# Shematic.net
KiCad netlist of a schematic drawn in Altium Designer
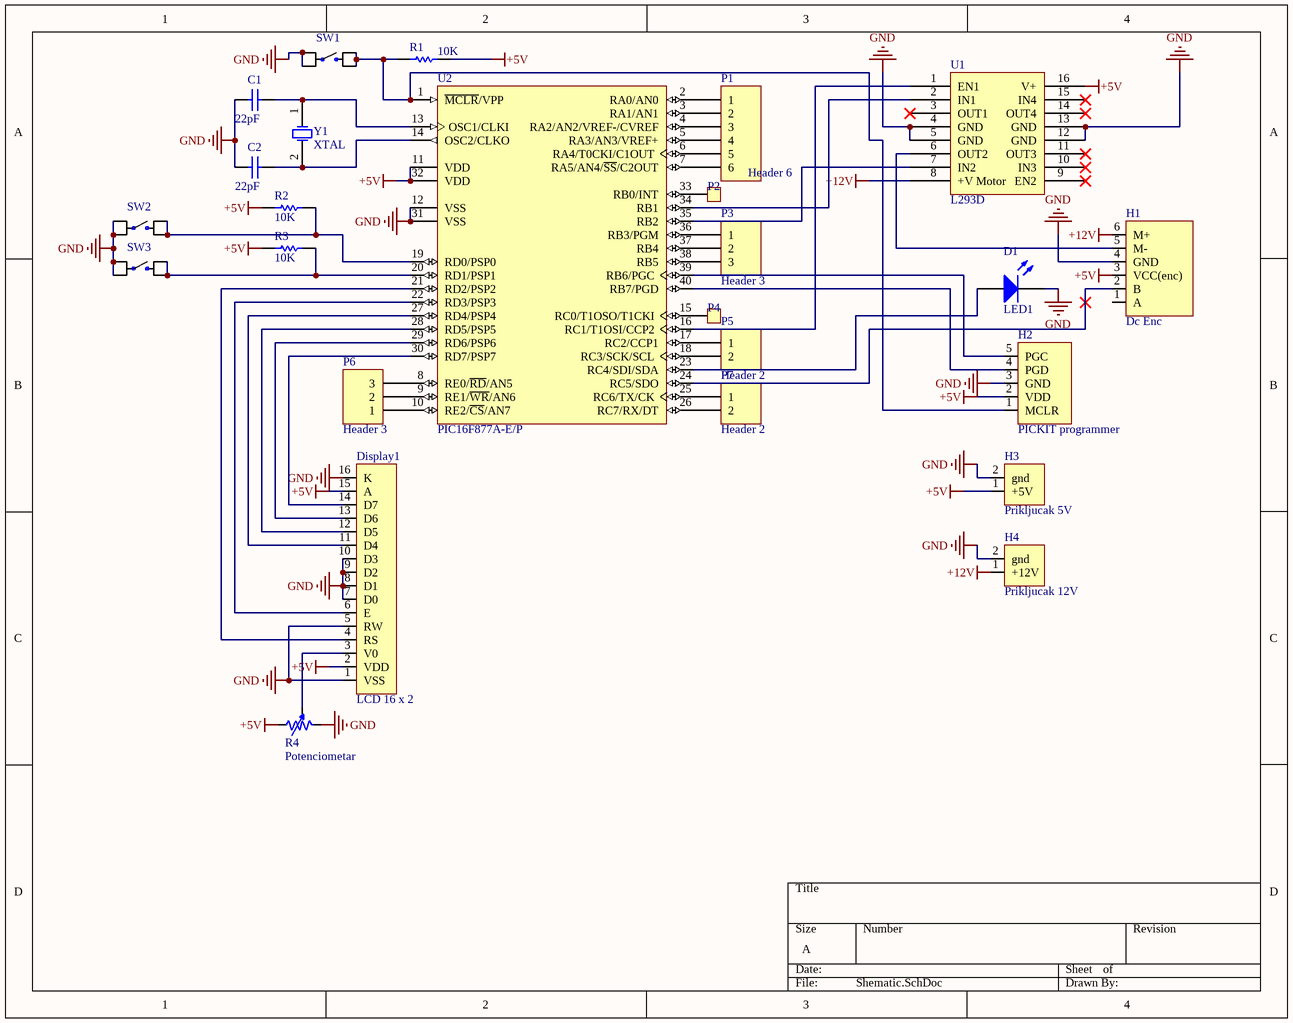
[diagram p0: Shematic.SchDoc]

(export (version "E")
  (design (tool "Eeschema 10.0.6"))
  (components
    (comp (ref "C1")
      (value "22pF")
      (footprint "RAD-0.3")
      (description "Capacitor")
      (fields (field (name "Comment") "Cap") (field (name "PUBLISHER") "Altium Limited"))
      (libsource (lib "Miscellaneous Devices") (part "Cap"))
    )
    (comp (ref "C2")
      (value "22pF")
      (footprint "RAD-0.3")
      (description "Capacitor")
      (fields (field (name "Comment") "Cap") (field (name "PUBLISHER") "Altium Limited"))
      (libsource (lib "Miscellaneous Devices") (part "Cap"))
    )
    (comp (ref "D1")
      (value "LED1")
      (footprint "LED-1")
      (description "Typical RED GaAs LED")
      (fields (field (name "PUBLISHER") "Altium Limited"))
      (libsource (lib "Miscellaneous Devices") (part "LED1"))
    )
    (comp (ref "Display1")
      (value "LCD 16 x 2")
      (footprint "LCD16x2")
      (libsource (lib "Shematic-LIB") (part "LCD 16 X 2"))
    )
    (comp (ref "H1") (value "Dc Enc") (libsource (lib "Shematic-LIB") (part "Header DC & ENC")))
    (comp (ref "H2")
      (value "PICKIT programmer")
      (footprint "Pickit")
      (libsource (lib "Shematic-LIB") (part "PICKIT HEADER"))
    )
    (comp (ref "H3")
      (value "Prikljucak 5V")
      (footprint "H 5V")
      (libsource (lib "Shematic-LIB") (part "Header 5V"))
    )
    (comp (ref "H4")
      (value "Prikljucak 12V")
      (footprint "H 12V")
      (libsource (lib "Shematic-LIB") (part "Header 12V"))
    )
    (comp (ref "P1")
      (value "Header 6")
      (footprint "HDR1X6")
      (description "Header, 6-Pin")
      (fields (field (name "PUBLISHER") "Altium Limited"))
      (libsource (lib "Miscellaneous Connectors") (part "Header 6"))
    )
    (comp (ref "P2")
      (value "Header 1")
      (footprint "Header 1")
      (libsource (lib "Shematic-LIB") (part "Header 1"))
    )
    (comp (ref "P3")
      (value "Header 3")
      (footprint "HDR1X3")
      (description "Header, 3-Pin")
      (fields (field (name "PUBLISHER") "Altium Limited"))
      (libsource (lib "") (part "Header 3_1"))
    )
    (comp (ref "P4")
      (value "Header 1")
      (footprint "Header 1")
      (libsource (lib "Shematic-LIB") (part "Header 1"))
    )
    (comp (ref "P5")
      (value "Header 2")
      (footprint "HDR1X2")
      (description "Header, 2-Pin")
      (fields (field (name "PUBLISHER") "Altium Limited"))
      (libsource (lib "Miscellaneous Connectors") (part "Header 2"))
    )
    (comp (ref "P6")
      (value "Header 3")
      (footprint "HDR1X3")
      (description "Header, 3-Pin")
      (fields (field (name "PUBLISHER") "Altium Limited"))
      (libsource (lib "Miscellaneous Connectors") (part "Header 3"))
    )
    (comp (ref "P7")
      (value "Header 2")
      (footprint "HDR1X2")
      (description "Header, 2-Pin")
      (fields (field (name "PUBLISHER") "Altium Limited"))
      (libsource (lib "Miscellaneous Connectors") (part "Header 2"))
    )
    (comp (ref "R1")
      (value "10K")
      (footprint "AXIAL-0.3")
      (description "Resistor")
      (fields (field (name "Comment") "Res1") (field (name "PUBLISHER") "Altium Limited"))
      (libsource (lib "Miscellaneous Devices") (part "Res1"))
    )
    (comp (ref "R2")
      (value "10K")
      (footprint "AXIAL-0.3")
      (description "Resistor")
      (fields (field (name "Comment") "Res1") (field (name "PUBLISHER") "Altium Limited"))
      (libsource (lib "Miscellaneous Devices") (part "Res1"))
    )
    (comp (ref "R3")
      (value "10K")
      (footprint "AXIAL-0.3")
      (description "Resistor")
      (fields (field (name "Comment") "Res1") (field (name "PUBLISHER") "Altium Limited"))
      (libsource (lib "Miscellaneous Devices") (part "Res1"))
    )
    (comp (ref "R4")
      (value "Potenciometar")
      (footprint "ADJ_RES")
      (libsource (lib "Shematic-LIB") (part "ADJ_RES"))
    )
    (comp (ref "SW1")
      (value "2-1437565-8")
      (footprint "*SW_SMD_2-1437565-8_4_4.50_6.00_6.00_5.00")
      (description "Tactile Switch SPST-NO Top Actuated Surface Mount")
      (fields (field (name "MF") "TE Connectivity"))
      (libsource (lib "Shematic-LIB") (part "2-1437565-8"))
    )
    (comp (ref "SW2")
      (value "2-1437565-8")
      (footprint "*SW_SMD_2-1437565-8_4_4.50_6.00_6.00_5.00")
      (description "Tactile Switch SPST-NO Top Actuated Surface Mount")
      (fields (field (name "MF") "TE Connectivity"))
      (libsource (lib "Shematic-LIB") (part "2-1437565-8"))
    )
    (comp (ref "SW3")
      (value "2-1437565-8")
      (footprint "*SW_SMD_2-1437565-8_4_4.50_6.00_6.00_5.00")
      (description "Tactile Switch SPST-NO Top Actuated Surface Mount")
      (fields (field (name "MF") "TE Connectivity"))
      (libsource (lib "Shematic-LIB") (part "2-1437565-8"))
    )
    (comp (ref "U1")
      (value "L293D")
      (footprint "*DIP880W50P254L2000H510Q16")
      (description "Motor Driver")
      (libsource (lib "Shematic-LIB") (part "L293D"))
    )
    (comp (ref "U2")
      (value "PIC16F877A-E/P")
      (footprint "*DIP254P1524X483-40")
      (fields (field (name "PUBLISHER") "Altium Limited"))
      (libsource (lib "Atmel Microcontroller 8-Bit AVR") (part "PIC16F877A-E/P"))
    )
    (comp (ref "Y1")
      (value "XTAL")
      (footprint "R38")
      (description "Crystal Oscillator")
      (fields (field (name "PUBLISHER") "Altium Limited"))
      (libsource (lib "Miscellaneous Devices") (part "XTAL"))
    )
  )
  (nets
    (net (code "1") (name "+5V") (class "Default")
      (node (ref "Display1") (pin "15") (pinfunction "A_15") (pintype "passive"))
      (node (ref "Display1") (pin "2") (pinfunction "VDD_2") (pintype "passive"))
      (node (ref "H1") (pin "3") (pinfunction "VCC(enc)_3") (pintype "passive"))
      (node (ref "H2") (pin "2") (pinfunction "VDD_2") (pintype "passive"))
      (node (ref "H3") (pin "1") (pinfunction "+5V_1") (pintype "passive"))
      (node (ref "R1") (pin "2") (pinfunction "2_2") (pintype "passive"))
      (node (ref "R2") (pin "2") (pinfunction "2_2") (pintype "passive"))
      (node (ref "R3") (pin "2") (pinfunction "2_2") (pintype "passive"))
      (node (ref "R4") (pin "1") (pinfunction "1_1") (pintype "passive"))
      (node (ref "U1") (pin "16") (pinfunction "V+_16") (pintype "passive"))
      (node (ref "U2") (pin "11") (pinfunction "VDD_11") (pintype "power_in"))
      (node (ref "U2") (pin "32") (pinfunction "VDD_32") (pintype "power_in"))
    )
    (net (code "2") (name "+12V") (class "Default")
      (node (ref "H1") (pin "6") (pinfunction "M+_6") (pintype "passive"))
      (node (ref "H4") (pin "1") (pinfunction "+12V_1") (pintype "passive"))
      (node (ref "U1") (pin "8") (pinfunction "+V_Motor_8") (pintype "passive"))
    )
    (net (code "3") (name "GND") (class "Default")
      (node (ref "C1") (pin "1") (pinfunction "1_1") (pintype "passive"))
      (node (ref "C2") (pin "1") (pinfunction "1_1") (pintype "passive"))
      (node (ref "D1") (pin "2") (pinfunction "K_2") (pintype "passive"))
      (node (ref "Display1") (pin "1") (pinfunction "VSS_1") (pintype "passive"))
      (node (ref "Display1") (pin "10") (pinfunction "D3_10") (pintype "passive"))
      (node (ref "Display1") (pin "16") (pinfunction "K_16") (pintype "passive"))
      (node (ref "Display1") (pin "5") (pinfunction "RW_5") (pintype "passive"))
      (node (ref "Display1") (pin "7") (pinfunction "D0_7") (pintype "passive"))
      (node (ref "Display1") (pin "8") (pinfunction "D1_8") (pintype "passive"))
      (node (ref "Display1") (pin "9") (pinfunction "D2_9") (pintype "passive"))
      (node (ref "H1") (pin "4") (pinfunction "GND_4") (pintype "passive"))
      (node (ref "H2") (pin "3") (pinfunction "GND_3") (pintype "passive"))
      (node (ref "H3") (pin "2") (pinfunction "gnd_2") (pintype "passive"))
      (node (ref "H4") (pin "2") (pinfunction "gnd_2") (pintype "passive"))
      (node (ref "R4") (pin "2") (pinfunction "2_2") (pintype "passive"))
      (node (ref "SW1") (pin "1") (pinfunction "1_1") (pintype "passive"))
      (node (ref "SW1") (pin "2") (pinfunction "2_2") (pintype "passive"))
      (node (ref "SW2") (pin "1") (pinfunction "1_1") (pintype "passive"))
      (node (ref "SW2") (pin "2") (pinfunction "2_2") (pintype "passive"))
      (node (ref "SW3") (pin "1") (pinfunction "1_1") (pintype "passive"))
      (node (ref "SW3") (pin "2") (pinfunction "2_2") (pintype "passive"))
      (node (ref "U1") (pin "12") (pinfunction "GND_12") (pintype "passive"))
      (node (ref "U1") (pin "13") (pinfunction "GND_13") (pintype "passive"))
      (node (ref "U1") (pin "4") (pinfunction "GND_4") (pintype "passive"))
      (node (ref "U1") (pin "5") (pinfunction "GND_5") (pintype "passive"))
      (node (ref "U2") (pin "12") (pinfunction "VSS_12") (pintype "power_in"))
      (node (ref "U2") (pin "31") (pinfunction "VSS_31") (pintype "power_in"))
    )
    (net (code "4") (name "Net-(D1-A)") (class "Default")
      (node (ref "D1") (pin "1") (pinfunction "A_1") (pintype "passive"))
      (node (ref "U2") (pin "23") (pinfunction "RC4/SDI/SDA_23") (pintype "bidirectional"))
    )
    (net (code "5") (name "Net-(Display1-D4)") (class "Default")
      (node (ref "Display1") (pin "11") (pinfunction "D4_11") (pintype "passive"))
      (node (ref "U2") (pin "27") (pinfunction "RD4/PSP4_27") (pintype "bidirectional"))
    )
    (net (code "6") (name "Net-(Display1-D5)") (class "Default")
      (node (ref "Display1") (pin "12") (pinfunction "D5_12") (pintype "passive"))
      (node (ref "U2") (pin "28") (pinfunction "RD5/PSP5_28") (pintype "bidirectional"))
    )
    (net (code "7") (name "Net-(Display1-D6)") (class "Default")
      (node (ref "Display1") (pin "13") (pinfunction "D6_13") (pintype "passive"))
      (node (ref "U2") (pin "29") (pinfunction "RD6/PSP6_29") (pintype "bidirectional"))
    )
    (net (code "8") (name "Net-(Display1-D7)") (class "Default")
      (node (ref "Display1") (pin "14") (pinfunction "D7_14") (pintype "passive"))
      (node (ref "U2") (pin "30") (pinfunction "RD7/PSP7_30") (pintype "bidirectional"))
    )
    (net (code "9") (name "Net-(Display1-E)") (class "Default")
      (node (ref "Display1") (pin "6") (pinfunction "E_6") (pintype "passive"))
      (node (ref "U2") (pin "22") (pinfunction "RD3/PSP3_22") (pintype "bidirectional"))
    )
    (net (code "10") (name "Net-(Display1-RS)") (class "Default")
      (node (ref "Display1") (pin "4") (pinfunction "RS_4") (pintype "passive"))
      (node (ref "U2") (pin "21") (pinfunction "RD2/PSP2_21") (pintype "bidirectional"))
    )
    (net (code "11") (name "Net-(Display1-V0)") (class "Default")
      (node (ref "Display1") (pin "3") (pinfunction "V0_3") (pintype "passive"))
      (node (ref "R4") (pin "3") (pinfunction "3_3") (pintype "passive"))
    )
    (net (code "12") (name "Net-(H1-B)") (class "Default")
      (node (ref "H1") (pin "2") (pinfunction "B_2") (pintype "passive"))
      (node (ref "U2") (pin "24") (pinfunction "RC5/SDO_24") (pintype "bidirectional"))
    )
    (net (code "13") (name "Net-(H1-M-)") (class "Default")
      (node (ref "H1") (pin "5") (pinfunction "M-_5") (pintype "passive"))
      (node (ref "U1") (pin "6") (pinfunction "OUT2_6") (pintype "passive"))
    )
    (net (code "14") (name "Net-(H2-MCLR)") (class "Default")
      (node (ref "H2") (pin "1") (pinfunction "MCLR_1") (pintype "passive"))
      (node (ref "R1") (pin "1") (pinfunction "1_1") (pintype "passive"))
      (node (ref "SW1") (pin "3") (pinfunction "3_3") (pintype "passive"))
      (node (ref "SW1") (pin "4") (pinfunction "4_4") (pintype "passive"))
      (node (ref "U2") (pin "1") (pinfunction "~{MCLR}/VPP_1") (pintype "input"))
    )
    (net (code "15") (name "Net-(H2-PGC)") (class "Default")
      (node (ref "H2") (pin "5") (pinfunction "PGC_5") (pintype "passive"))
      (node (ref "U2") (pin "39") (pinfunction "RB6/PGC_39") (pintype "bidirectional"))
    )
    (net (code "16") (name "Net-(H2-PGD)") (class "Default")
      (node (ref "H2") (pin "4") (pinfunction "PGD_4") (pintype "passive"))
      (node (ref "U2") (pin "40") (pinfunction "RB7/PGD_40") (pintype "bidirectional"))
    )
    (net (code "17") (name "Net-(U1-EN1)") (class "Default")
      (node (ref "U1") (pin "1") (pinfunction "EN1_1") (pintype "passive"))
      (node (ref "U2") (pin "16") (pinfunction "RC1/T1OSI/CCP2_16") (pintype "bidirectional"))
    )
    (net (code "18") (name "Net-(U1-IN1)") (class "Default")
      (node (ref "U1") (pin "2") (pinfunction "IN1_2") (pintype "passive"))
      (node (ref "U2") (pin "34") (pinfunction "RB1_34") (pintype "bidirectional"))
    )
    (net (code "19") (name "Net-(U1-IN2)") (class "Default")
      (node (ref "U1") (pin "7") (pinfunction "IN2_7") (pintype "passive"))
      (node (ref "U2") (pin "35") (pinfunction "RB2_35") (pintype "bidirectional"))
    )
    (net (code "20") (name "Net-(U2-OSC1{slash}CLKI)") (class "Default")
      (node (ref "C1") (pin "2") (pinfunction "2_2") (pintype "passive"))
      (node (ref "U2") (pin "13") (pinfunction "OSC1/CLKI_13") (pintype "input"))
      (node (ref "Y1") (pin "1") (pinfunction "OSC1_1") (pintype "passive"))
    )
    (net (code "21") (name "Net-(U2-OSC2{slash}CLKO)") (class "Default")
      (node (ref "C2") (pin "2") (pinfunction "2_2") (pintype "passive"))
      (node (ref "U2") (pin "14") (pinfunction "OSC2/CLKO_14") (pintype "output"))
      (node (ref "Y1") (pin "2") (pinfunction "OSC2_2") (pintype "passive"))
    )
    (net (code "22") (name "Net-(U2-RA0{slash}AN0)") (class "Default")
      (node (ref "P1") (pin "1") (pinfunction "1_1") (pintype "passive"))
      (node (ref "U2") (pin "2") (pinfunction "RA0/AN0_2") (pintype "bidirectional"))
    )
    (net (code "23") (name "Net-(U2-RA1{slash}AN1)") (class "Default")
      (node (ref "P1") (pin "2") (pinfunction "2_2") (pintype "passive"))
      (node (ref "U2") (pin "3") (pinfunction "RA1/AN1_3") (pintype "bidirectional"))
    )
    (net (code "24") (name "Net-(U2-RA2{slash}AN2{slash}VREF-{slash}CVREF)") (class "Default")
      (node (ref "P1") (pin "3") (pinfunction "3_3") (pintype "passive"))
      (node (ref "U2") (pin "4") (pinfunction "RA2/AN2/VREF-/CVREF_4") (pintype "bidirectional"))
    )
    (net (code "25") (name "Net-(U2-RA3{slash}AN3{slash}VREF+)") (class "Default")
      (node (ref "P1") (pin "4") (pinfunction "4_4") (pintype "passive"))
      (node (ref "U2") (pin "5") (pinfunction "RA3/AN3/VREF+_5") (pintype "bidirectional"))
    )
    (net (code "26") (name "Net-(U2-RA4{slash}T0CKI{slash}C1OUT)") (class "Default")
      (node (ref "P1") (pin "5") (pinfunction "5_5") (pintype "passive"))
      (node (ref "U2") (pin "6") (pinfunction "RA4/T0CKI/C1OUT_6") (pintype "bidirectional"))
    )
    (net (code "27") (name "Net-(U2-RA5{slash}AN4{slash}~{SS}{slash}C2OUT)") (class "Default")
      (node (ref "P1") (pin "6") (pinfunction "6_6") (pintype "passive"))
      (node (ref "U2") (pin "7") (pinfunction "RA5/AN4/~{SS}/C2OUT_7") (pintype "bidirectional"))
    )
    (net (code "28") (name "Net-(U2-RB0{slash}INT)") (class "Default")
      (node (ref "P2") (pin "1") (pinfunction "1_1") (pintype "passive"))
      (node (ref "U2") (pin "33") (pinfunction "RB0/INT_33") (pintype "bidirectional"))
    )
    (net (code "29") (name "Net-(U2-RB3{slash}PGM)") (class "Default")
      (node (ref "P3") (pin "1") (pinfunction "1_1") (pintype "passive"))
      (node (ref "U2") (pin "36") (pinfunction "RB3/PGM_36") (pintype "bidirectional"))
    )
    (net (code "30") (name "Net-(U2-RB4)") (class "Default")
      (node (ref "P3") (pin "2") (pinfunction "2_2") (pintype "passive"))
      (node (ref "U2") (pin "37") (pinfunction "RB4_37") (pintype "bidirectional"))
    )
    (net (code "31") (name "Net-(U2-RB5)") (class "Default")
      (node (ref "P3") (pin "3") (pinfunction "3_3") (pintype "passive"))
      (node (ref "U2") (pin "38") (pinfunction "RB5_38") (pintype "bidirectional"))
    )
    (net (code "32") (name "Net-(U2-RC0{slash}T1OSO{slash}T1CKI)") (class "Default")
      (node (ref "P4") (pin "1") (pinfunction "1_1") (pintype "passive"))
      (node (ref "U2") (pin "15") (pinfunction "RC0/T1OSO/T1CKI_15") (pintype "bidirectional"))
    )
    (net (code "33") (name "Net-(U2-RC2{slash}CCP1)") (class "Default")
      (node (ref "P5") (pin "1") (pinfunction "1_1") (pintype "passive"))
      (node (ref "U2") (pin "17") (pinfunction "RC2/CCP1_17") (pintype "bidirectional"))
    )
    (net (code "34") (name "Net-(U2-RC3{slash}SCK{slash}SCL)") (class "Default")
      (node (ref "P5") (pin "2") (pinfunction "2_2") (pintype "passive"))
      (node (ref "U2") (pin "18") (pinfunction "RC3/SCK/SCL_18") (pintype "bidirectional"))
    )
    (net (code "35") (name "Net-(U2-RC6{slash}TX{slash}CK)") (class "Default")
      (node (ref "P7") (pin "1") (pinfunction "1_1") (pintype "passive"))
      (node (ref "U2") (pin "25") (pinfunction "RC6/TX/CK_25") (pintype "bidirectional"))
    )
    (net (code "36") (name "Net-(U2-RC7{slash}RX{slash}DT)") (class "Default")
      (node (ref "P7") (pin "2") (pinfunction "2_2") (pintype "passive"))
      (node (ref "U2") (pin "26") (pinfunction "RC7/RX/DT_26") (pintype "bidirectional"))
    )
    (net (code "37") (name "Net-(U2-RD0{slash}PSP0)") (class "Default")
      (node (ref "R2") (pin "1") (pinfunction "1_1") (pintype "passive"))
      (node (ref "SW2") (pin "3") (pinfunction "3_3") (pintype "passive"))
      (node (ref "SW2") (pin "4") (pinfunction "4_4") (pintype "passive"))
      (node (ref "U2") (pin "19") (pinfunction "RD0/PSP0_19") (pintype "bidirectional"))
    )
    (net (code "38") (name "Net-(U2-RD1{slash}PSP1)") (class "Default")
      (node (ref "R3") (pin "1") (pinfunction "1_1") (pintype "passive"))
      (node (ref "SW3") (pin "3") (pinfunction "3_3") (pintype "passive"))
      (node (ref "SW3") (pin "4") (pinfunction "4_4") (pintype "passive"))
      (node (ref "U2") (pin "20") (pinfunction "RD1/PSP1_20") (pintype "bidirectional"))
    )
    (net (code "39") (name "Net-(U2-RE0{slash}~{RD}{slash}AN5)") (class "Default")
      (node (ref "P6") (pin "3") (pinfunction "3_3") (pintype "passive"))
      (node (ref "U2") (pin "8") (pinfunction "RE0/~{RD}/AN5_8") (pintype "bidirectional"))
    )
    (net (code "40") (name "Net-(U2-RE1{slash}~{WR}{slash}AN6)") (class "Default")
      (node (ref "P6") (pin "2") (pinfunction "2_2") (pintype "passive"))
      (node (ref "U2") (pin "9") (pinfunction "RE1/~{WR}/AN6_9") (pintype "bidirectional"))
    )
    (net (code "41") (name "Net-(U2-RE2{slash}~{CS}{slash}AN7)") (class "Default")
      (node (ref "P6") (pin "1") (pinfunction "1_1") (pintype "passive"))
      (node (ref "U2") (pin "10") (pinfunction "RE2/~{CS}/AN7_10") (pintype "bidirectional"))
    )
    (net (code "42") (name "unconnected-(H1-A-Pad1)") (class "Default")
      (node (ref "H1") (pin "1") (pinfunction "A_1") (pintype "passive"))
    )
    (net (code "43") (name "unconnected-(U1-EN2-Pad9)") (class "Default")
      (node (ref "U1") (pin "9") (pinfunction "EN2_9") (pintype "passive+no_connect"))
    )
    (net (code "44") (name "unconnected-(U1-IN3-Pad10)") (class "Default")
      (node (ref "U1") (pin "10") (pinfunction "IN3_10") (pintype "passive+no_connect"))
    )
    (net (code "45") (name "unconnected-(U1-IN4-Pad15)") (class "Default")
      (node (ref "U1") (pin "15") (pinfunction "IN4_15") (pintype "passive+no_connect"))
    )
    (net (code "46") (name "unconnected-(U1-OUT1-Pad3)") (class "Default")
      (node (ref "U1") (pin "3") (pinfunction "OUT1_3") (pintype "passive+no_connect"))
    )
    (net (code "47") (name "unconnected-(U1-OUT3-Pad11)") (class "Default")
      (node (ref "U1") (pin "11") (pinfunction "OUT3_11") (pintype "passive+no_connect"))
    )
    (net (code "48") (name "unconnected-(U1-OUT4-Pad14)") (class "Default")
      (node (ref "U1") (pin "14") (pinfunction "OUT4_14") (pintype "passive+no_connect"))
    )
  )
)
